# shiva.net
KiCad netlist of a schematic drawn in EAGLE
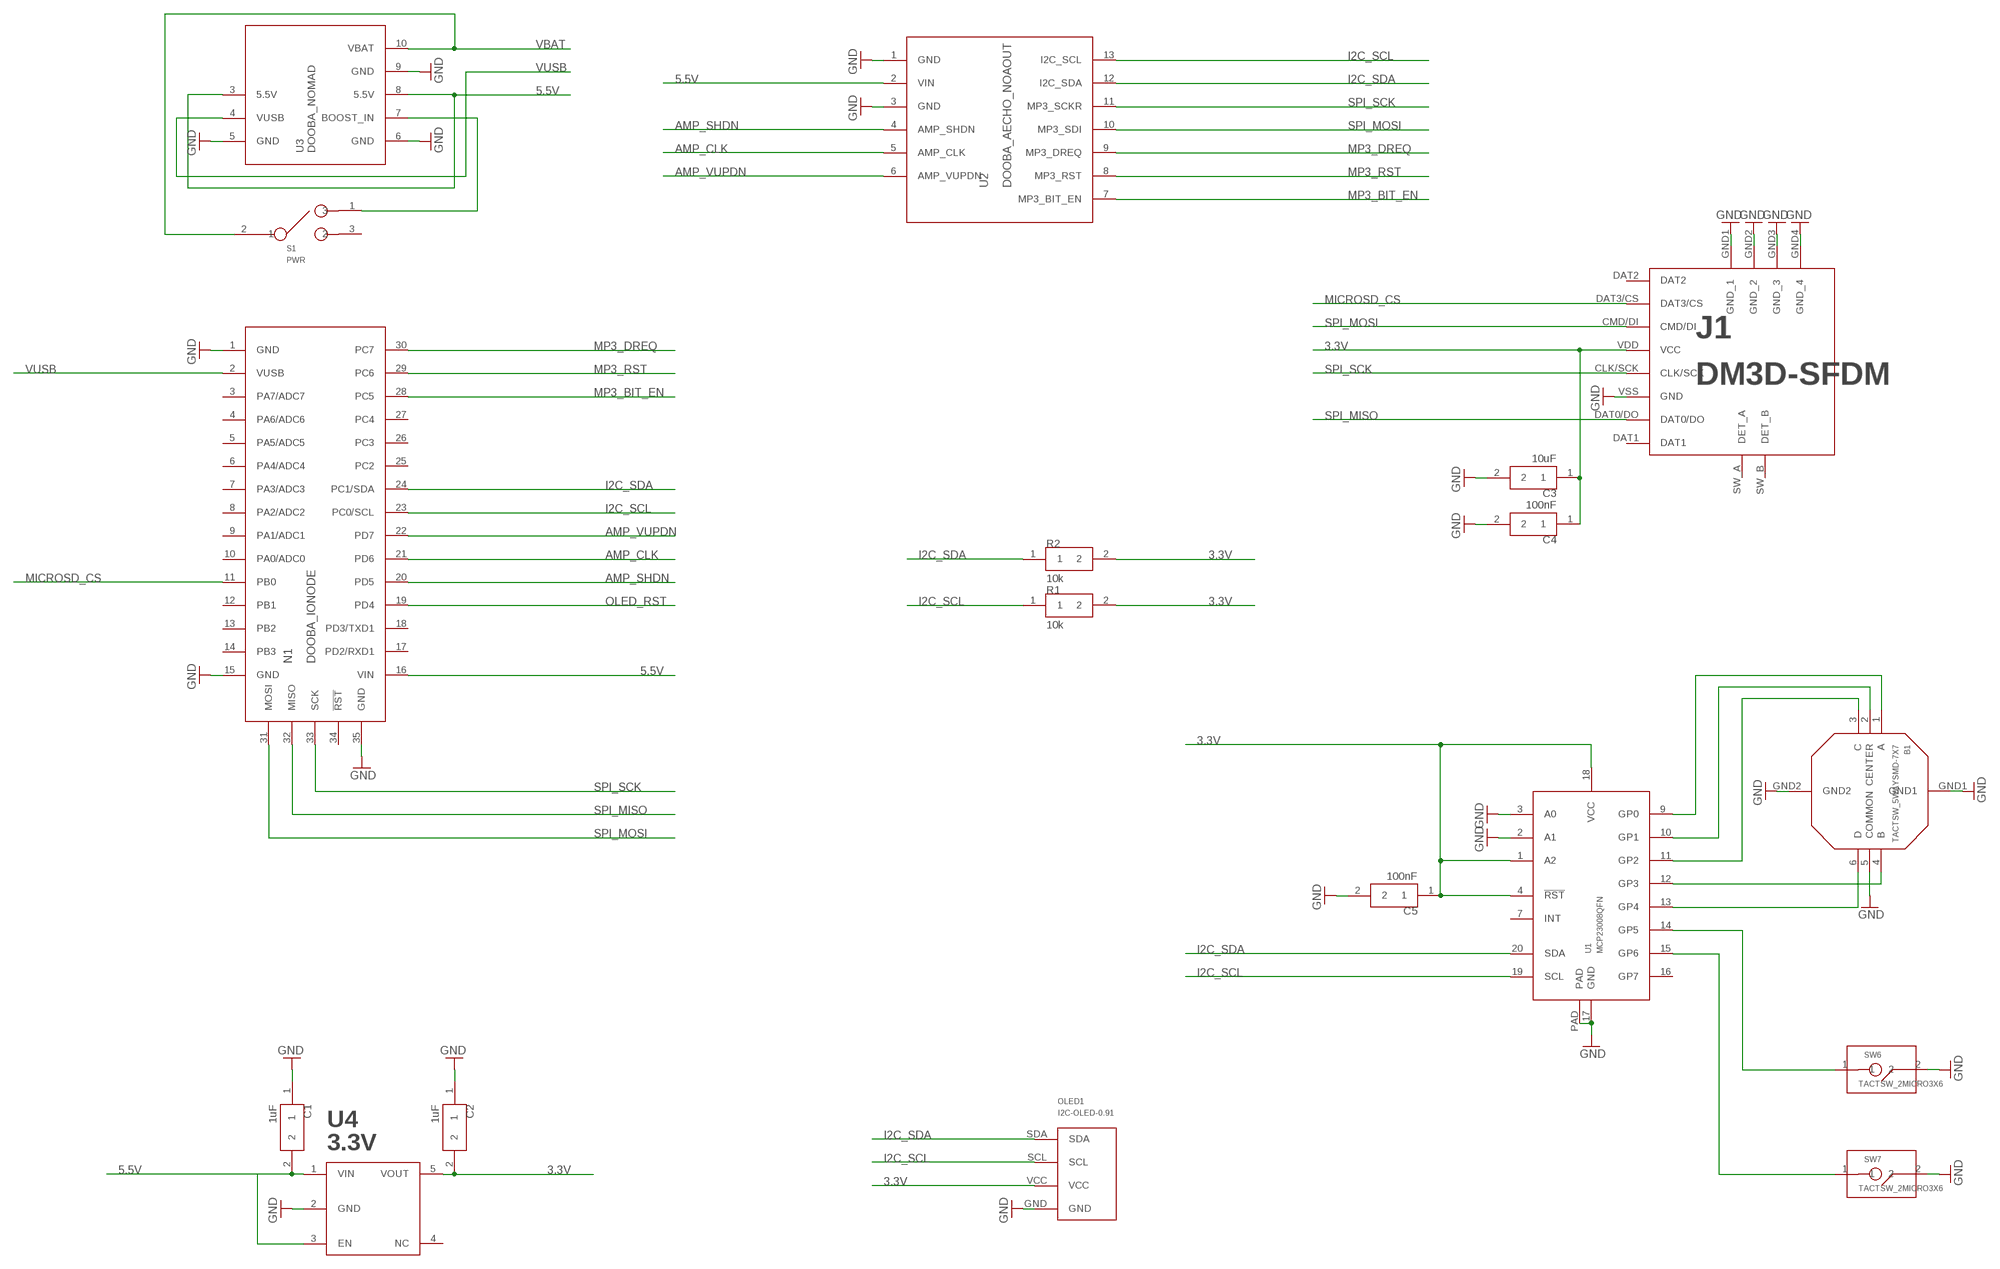
[diagram p0: schematic, sheet 1]

(export (version "E")
  (design (tool "Eeschema 10.0.6"))
  (components
    (comp (ref "B1")
      (value "TACTSW_5WAYSMD-7X7")
      (footprint "eagle-import:TACTSW-5WAY-7X7")
      (libsource (lib "eagle-import") (part "TACTSW_5WAYSMD-7X7"))
    )
    (comp (ref "C1")
      (value "1uF")
      (footprint "eagle-import:0805")
      (libsource (lib "eagle-import") (part "CAP0805"))
    )
    (comp (ref "C2")
      (value "1uF")
      (footprint "eagle-import:0805")
      (libsource (lib "eagle-import") (part "CAP0805"))
    )
    (comp (ref "C3")
      (value "10uF")
      (footprint "eagle-import:0805")
      (libsource (lib "eagle-import") (part "CAP0805"))
    )
    (comp (ref "C4")
      (value "100nF")
      (footprint "eagle-import:0805")
      (libsource (lib "eagle-import") (part "CAP0805"))
    )
    (comp (ref "C5")
      (value "100nF")
      (footprint "eagle-import:0805")
      (libsource (lib "eagle-import") (part "CAP0805"))
    )
    (comp (ref "J1")
      (value "DM3D-SFDM")
      (footprint "eagle-import:DM3D-SF")
      (libsource (lib "eagle-import") (part "DM3D-SFDM"))
    )
    (comp (ref "N1")
      (value "DOOBA_IONODE")
      (footprint "eagle-import:DOOBA_IONODE")
      (libsource (lib "eagle-import") (part "DOOBA_IONODE"))
    )
    (comp (ref "OLED1")
      (value "I2C-OLED-0.91")
      (footprint "eagle-import:I2C-OLED-0.91")
      (libsource (lib "eagle-import") (part "I2C-OLED-0.91"))
    )
    (comp (ref "R1")
      (value "10k")
      (footprint "eagle-import:0805")
      (libsource (lib "eagle-import") (part "RES0805"))
    )
    (comp (ref "R2")
      (value "10k")
      (footprint "eagle-import:0805")
      (libsource (lib "eagle-import") (part "RES0805"))
    )
    (comp (ref "S1")
      (value "PWR")
      (footprint "eagle-import:JS102011")
      (libsource (lib "eagle-import") (part "SWITCH_SPDT"))
    )
    (comp (ref "SW6")
      (value "TACTSW_2MICRO3X6")
      (footprint "eagle-import:TACTSW_MICRO3X6")
      (libsource (lib "eagle-import") (part "TACTSW_2MICRO3X6"))
    )
    (comp (ref "SW7")
      (value "TACTSW_2MICRO3X6")
      (footprint "eagle-import:TACTSW_MICRO3X6")
      (libsource (lib "eagle-import") (part "TACTSW_2MICRO3X6"))
    )
    (comp (ref "U1")
      (value "MCP23008QFN")
      (footprint "eagle-import:20-VQFN")
      (libsource (lib "eagle-import") (part "MCP23008QFN"))
    )
    (comp (ref "U2")
      (value "DOOBA_AECHO_NOAOUT")
      (footprint "eagle-import:DOOBA_AECHO_NOAOUT")
      (libsource (lib "eagle-import") (part "DOOBA_AECHO_NOAOUT"))
    )
    (comp (ref "U3")
      (value "DOOBA_NOMAD")
      (footprint "eagle-import:DOOBA_NOMAD")
      (libsource (lib "eagle-import") (part "DOOBA_NOMAD"))
    )
    (comp (ref "U4")
      (value "3.3V")
      (footprint "eagle-import:SOT23-5")
      (libsource (lib "eagle-import") (part "LP3985SOT23-5"))
    )
  )
  (nets
    (net (code "1") (name "/3.3V") (class "Default")
      (node (ref "C2") (pin "2") (pinfunction "2_2") (pintype "bidirectional"))
      (node (ref "C3") (pin "1") (pinfunction "1_1") (pintype "bidirectional"))
      (node (ref "C4") (pin "1") (pinfunction "1_1") (pintype "bidirectional"))
      (node (ref "C5") (pin "1") (pinfunction "1_1") (pintype "bidirectional"))
      (node (ref "J1") (pin "VDD") (pinfunction "VCC_VDD") (pintype "bidirectional"))
      (node (ref "OLED1") (pin "VCC") (pinfunction "VCC_VCC") (pintype "bidirectional"))
      (node (ref "R1") (pin "2") (pinfunction "2_2") (pintype "bidirectional"))
      (node (ref "R2") (pin "2") (pinfunction "2_2") (pintype "bidirectional"))
      (node (ref "U1") (pin "1") (pinfunction "A2_1") (pintype "bidirectional"))
      (node (ref "U1") (pin "18") (pinfunction "VCC_18") (pintype "bidirectional"))
      (node (ref "U1") (pin "4") (pinfunction "~{RST}_4") (pintype "bidirectional"))
      (node (ref "U4") (pin "5") (pinfunction "VOUT_5") (pintype "bidirectional"))
    )
    (net (code "2") (name "/5.5V") (class "Default")
      (node (ref "C1") (pin "2") (pinfunction "2_2") (pintype "bidirectional"))
      (node (ref "N1") (pin "16") (pinfunction "VIN_16") (pintype "bidirectional"))
      (node (ref "U2") (pin "2") (pinfunction "VIN_2") (pintype "bidirectional"))
      (node (ref "U3") (pin "3") (pinfunction "5.5V_3") (pintype "bidirectional"))
      (node (ref "U3") (pin "8") (pinfunction "5.5V_8") (pintype "bidirectional"))
      (node (ref "U4") (pin "1") (pinfunction "VIN_1") (pintype "bidirectional"))
      (node (ref "U4") (pin "3") (pinfunction "EN_3") (pintype "bidirectional"))
    )
    (net (code "3") (name "/AMP_CLK") (class "Default")
      (node (ref "N1") (pin "21") (pinfunction "PD6_21") (pintype "bidirectional"))
      (node (ref "U2") (pin "5") (pinfunction "AMP_CLK_5") (pintype "bidirectional"))
    )
    (net (code "4") (name "/AMP_SHDN") (class "Default")
      (node (ref "N1") (pin "20") (pinfunction "PD5_20") (pintype "bidirectional"))
      (node (ref "U2") (pin "4") (pinfunction "AMP_SHDN_4") (pintype "bidirectional"))
    )
    (net (code "5") (name "/AMP_VUPDN") (class "Default")
      (node (ref "N1") (pin "22") (pinfunction "PD7_22") (pintype "bidirectional"))
      (node (ref "U2") (pin "6") (pinfunction "AMP_VUPDN_6") (pintype "bidirectional"))
    )
    (net (code "6") (name "/I2C_SCL") (class "Default")
      (node (ref "N1") (pin "23") (pinfunction "PC0/SCL_23") (pintype "bidirectional"))
      (node (ref "OLED1") (pin "SCL") (pinfunction "SCL_SCL") (pintype "bidirectional"))
      (node (ref "R1") (pin "1") (pinfunction "1_1") (pintype "bidirectional"))
      (node (ref "U1") (pin "19") (pinfunction "SCL_19") (pintype "bidirectional"))
      (node (ref "U2") (pin "13") (pinfunction "I2C_SCL_13") (pintype "bidirectional"))
    )
    (net (code "7") (name "/I2C_SDA") (class "Default")
      (node (ref "N1") (pin "24") (pinfunction "PC1/SDA_24") (pintype "bidirectional"))
      (node (ref "OLED1") (pin "SDA") (pinfunction "SDA_SDA") (pintype "bidirectional"))
      (node (ref "R2") (pin "1") (pinfunction "1_1") (pintype "bidirectional"))
      (node (ref "U1") (pin "20") (pinfunction "SDA_20") (pintype "bidirectional"))
      (node (ref "U2") (pin "12") (pinfunction "I2C_SDA_12") (pintype "bidirectional"))
    )
    (net (code "8") (name "/MICROSD_CS") (class "Default")
      (node (ref "J1") (pin "DAT3/CS") (pinfunction "DAT3/CS_DAT3/CS") (pintype "bidirectional"))
      (node (ref "N1") (pin "11") (pinfunction "PB0_11") (pintype "bidirectional"))
    )
    (net (code "9") (name "/MP3_BIT_EN") (class "Default")
      (node (ref "N1") (pin "28") (pinfunction "PC5_28") (pintype "bidirectional"))
      (node (ref "U2") (pin "7") (pinfunction "MP3_BIT_EN_7") (pintype "bidirectional"))
    )
    (net (code "10") (name "/MP3_DREQ") (class "Default")
      (node (ref "N1") (pin "30") (pinfunction "PC7_30") (pintype "bidirectional"))
      (node (ref "U2") (pin "9") (pinfunction "MP3_DREQ_9") (pintype "bidirectional"))
    )
    (net (code "11") (name "/MP3_RST") (class "Default")
      (node (ref "N1") (pin "29") (pinfunction "PC6_29") (pintype "bidirectional"))
      (node (ref "U2") (pin "8") (pinfunction "MP3_RST_8") (pintype "bidirectional"))
    )
    (net (code "12") (name "/OLED_RST") (class "Default")
      (node (ref "N1") (pin "19") (pinfunction "PD4_19") (pintype "bidirectional"))
    )
    (net (code "13") (name "/SPI_MISO") (class "Default")
      (node (ref "J1") (pin "DAT0/DO") (pinfunction "DAT0/DO_DAT0/DO") (pintype "bidirectional"))
      (node (ref "N1") (pin "32") (pinfunction "MISO_32") (pintype "bidirectional"))
    )
    (net (code "14") (name "/SPI_MOSI") (class "Default")
      (node (ref "J1") (pin "CMD/DI") (pinfunction "CMD/DI_CMD/DI") (pintype "bidirectional"))
      (node (ref "N1") (pin "31") (pinfunction "MOSI_31") (pintype "bidirectional"))
      (node (ref "U2") (pin "10") (pinfunction "MP3_SDI_10") (pintype "bidirectional"))
    )
    (net (code "15") (name "/SPI_SCK") (class "Default")
      (node (ref "J1") (pin "CLK/SCK") (pinfunction "CLK/SCK_CLK/SCK") (pintype "bidirectional"))
      (node (ref "N1") (pin "33") (pinfunction "SCK_33") (pintype "bidirectional"))
      (node (ref "U2") (pin "11") (pinfunction "MP3_SCKR_11") (pintype "bidirectional"))
    )
    (net (code "16") (name "/VBAT") (class "Default")
      (node (ref "S1") (pin "2") (pinfunction "1_2") (pintype "bidirectional"))
      (node (ref "U3") (pin "10") (pinfunction "VBAT_10") (pintype "bidirectional"))
    )
    (net (code "17") (name "/VUSB") (class "Default")
      (node (ref "N1") (pin "2") (pinfunction "VUSB_2") (pintype "bidirectional"))
      (node (ref "U3") (pin "4") (pinfunction "VUSB_4") (pintype "bidirectional"))
    )
    (net (code "18") (name "GND") (class "Default")
      (node (ref "B1") (pin "5") (pinfunction "COMMON_5") (pintype "bidirectional"))
      (node (ref "B1") (pin "GND1") (pinfunction "GND1_GND1") (pintype "bidirectional"))
      (node (ref "B1") (pin "GND2") (pinfunction "GND2_GND2") (pintype "bidirectional"))
      (node (ref "C1") (pin "1") (pinfunction "1_1") (pintype "bidirectional"))
      (node (ref "C2") (pin "1") (pinfunction "1_1") (pintype "bidirectional"))
      (node (ref "C3") (pin "2") (pinfunction "2_2") (pintype "bidirectional"))
      (node (ref "C4") (pin "2") (pinfunction "2_2") (pintype "bidirectional"))
      (node (ref "C5") (pin "2") (pinfunction "2_2") (pintype "bidirectional"))
      (node (ref "J1") (pin "GND1") (pinfunction "GND_1_GND1") (pintype "bidirectional"))
      (node (ref "J1") (pin "GND2") (pinfunction "GND_2_GND2") (pintype "bidirectional"))
      (node (ref "J1") (pin "GND3") (pinfunction "GND_3_GND3") (pintype "bidirectional"))
      (node (ref "J1") (pin "GND4") (pinfunction "GND_4_GND4") (pintype "bidirectional"))
      (node (ref "J1") (pin "VSS") (pinfunction "GND_VSS") (pintype "bidirectional"))
      (node (ref "N1") (pin "1") (pinfunction "GND_1") (pintype "bidirectional"))
      (node (ref "N1") (pin "15") (pinfunction "GND_15") (pintype "bidirectional"))
      (node (ref "N1") (pin "35") (pinfunction "GND_35") (pintype "bidirectional"))
      (node (ref "OLED1") (pin "GND") (pinfunction "GND_GND") (pintype "bidirectional"))
      (node (ref "SW6") (pin "2") (pinfunction "2_2") (pintype "bidirectional"))
      (node (ref "SW7") (pin "2") (pinfunction "2_2") (pintype "bidirectional"))
      (node (ref "U1") (pin "17") (pinfunction "GND_17") (pintype "bidirectional"))
      (node (ref "U1") (pin "2") (pinfunction "A1_2") (pintype "bidirectional"))
      (node (ref "U1") (pin "3") (pinfunction "A0_3") (pintype "bidirectional"))
      (node (ref "U1") (pin "PAD") (pinfunction "PAD_PAD") (pintype "bidirectional"))
      (node (ref "U2") (pin "1") (pinfunction "GND_1") (pintype "bidirectional"))
      (node (ref "U2") (pin "3") (pinfunction "GND_3") (pintype "bidirectional"))
      (node (ref "U3") (pin "5") (pinfunction "GND_5") (pintype "bidirectional"))
      (node (ref "U3") (pin "6") (pinfunction "GND_6") (pintype "bidirectional"))
      (node (ref "U3") (pin "9") (pinfunction "GND_9") (pintype "bidirectional"))
      (node (ref "U4") (pin "2") (pinfunction "GND_2") (pintype "bidirectional"))
    )
    (net (code "19") (name "Net-(B1-A)") (class "Default")
      (node (ref "B1") (pin "1") (pinfunction "A_1") (pintype "bidirectional"))
      (node (ref "U1") (pin "9") (pinfunction "GP0_9") (pintype "bidirectional"))
    )
    (net (code "20") (name "Net-(B1-B)") (class "Default")
      (node (ref "B1") (pin "4") (pinfunction "B_4") (pintype "bidirectional"))
      (node (ref "U1") (pin "12") (pinfunction "GP3_12") (pintype "bidirectional"))
    )
    (net (code "21") (name "Net-(B1-C)") (class "Default")
      (node (ref "B1") (pin "3") (pinfunction "C_3") (pintype "bidirectional"))
      (node (ref "U1") (pin "11") (pinfunction "GP2_11") (pintype "bidirectional"))
    )
    (net (code "22") (name "Net-(B1-CENTER)") (class "Default")
      (node (ref "B1") (pin "2") (pinfunction "CENTER_2") (pintype "bidirectional"))
      (node (ref "U1") (pin "10") (pinfunction "GP1_10") (pintype "bidirectional"))
    )
    (net (code "23") (name "Net-(B1-D)") (class "Default")
      (node (ref "B1") (pin "6") (pinfunction "D_6") (pintype "bidirectional"))
      (node (ref "U1") (pin "13") (pinfunction "GP4_13") (pintype "bidirectional"))
    )
    (net (code "24") (name "Net-(S1-3)") (class "Default")
      (node (ref "S1") (pin "1") (pinfunction "3_1") (pintype "bidirectional"))
      (node (ref "U3") (pin "7") (pinfunction "BOOST_IN_7") (pintype "bidirectional"))
    )
    (net (code "25") (name "Net-(U1-GP5)") (class "Default")
      (node (ref "SW6") (pin "1") (pinfunction "1_1") (pintype "bidirectional"))
      (node (ref "U1") (pin "14") (pinfunction "GP5_14") (pintype "bidirectional"))
    )
    (net (code "26") (name "Net-(U1-GP6)") (class "Default")
      (node (ref "SW7") (pin "1") (pinfunction "1_1") (pintype "bidirectional"))
      (node (ref "U1") (pin "15") (pinfunction "GP6_15") (pintype "bidirectional"))
    )
    (net (code "27") (name "unconnected-(J1-DET_A-PadSW_A)") (class "Default")
      (node (ref "J1") (pin "SW_A") (pinfunction "DET_A_SW_A") (pintype "bidirectional"))
    )
    (net (code "28") (name "unconnected-(J1-DET_B-PadSW_B)") (class "Default")
      (node (ref "J1") (pin "SW_B") (pinfunction "DET_B_SW_B") (pintype "bidirectional"))
    )
    (net (code "29") (name "unconnected-(J1-PadDAT1)") (class "Default")
      (node (ref "J1") (pin "DAT1") (pinfunction "DAT1_DAT1") (pintype "bidirectional"))
    )
    (net (code "30") (name "unconnected-(J1-PadDAT2)") (class "Default")
      (node (ref "J1") (pin "DAT2") (pinfunction "DAT2_DAT2") (pintype "bidirectional"))
    )
    (net (code "31") (name "unconnected-(N1-PA0{slash}ADC0-Pad10)") (class "Default")
      (node (ref "N1") (pin "10") (pinfunction "PA0/ADC0_10") (pintype "bidirectional"))
    )
    (net (code "32") (name "unconnected-(N1-PA1{slash}ADC1-Pad9)") (class "Default")
      (node (ref "N1") (pin "9") (pinfunction "PA1/ADC1_9") (pintype "bidirectional"))
    )
    (net (code "33") (name "unconnected-(N1-PA2{slash}ADC2-Pad8)") (class "Default")
      (node (ref "N1") (pin "8") (pinfunction "PA2/ADC2_8") (pintype "bidirectional"))
    )
    (net (code "34") (name "unconnected-(N1-PA3{slash}ADC3-Pad7)") (class "Default")
      (node (ref "N1") (pin "7") (pinfunction "PA3/ADC3_7") (pintype "bidirectional"))
    )
    (net (code "35") (name "unconnected-(N1-PA4{slash}ADC4-Pad6)") (class "Default")
      (node (ref "N1") (pin "6") (pinfunction "PA4/ADC4_6") (pintype "bidirectional"))
    )
    (net (code "36") (name "unconnected-(N1-PA5{slash}ADC5-Pad5)") (class "Default")
      (node (ref "N1") (pin "5") (pinfunction "PA5/ADC5_5") (pintype "bidirectional"))
    )
    (net (code "37") (name "unconnected-(N1-PA6{slash}ADC6-Pad4)") (class "Default")
      (node (ref "N1") (pin "4") (pinfunction "PA6/ADC6_4") (pintype "bidirectional"))
    )
    (net (code "38") (name "unconnected-(N1-PA7{slash}ADC7-Pad3)") (class "Default")
      (node (ref "N1") (pin "3") (pinfunction "PA7/ADC7_3") (pintype "bidirectional"))
    )
    (net (code "39") (name "unconnected-(N1-PB1-Pad12)") (class "Default")
      (node (ref "N1") (pin "12") (pinfunction "PB1_12") (pintype "bidirectional"))
    )
    (net (code "40") (name "unconnected-(N1-PB2-Pad13)") (class "Default")
      (node (ref "N1") (pin "13") (pinfunction "PB2_13") (pintype "bidirectional"))
    )
    (net (code "41") (name "unconnected-(N1-PB3-Pad14)") (class "Default")
      (node (ref "N1") (pin "14") (pinfunction "PB3_14") (pintype "bidirectional"))
    )
    (net (code "42") (name "unconnected-(N1-PC2-Pad25)") (class "Default")
      (node (ref "N1") (pin "25") (pinfunction "PC2_25") (pintype "bidirectional"))
    )
    (net (code "43") (name "unconnected-(N1-PC3-Pad26)") (class "Default")
      (node (ref "N1") (pin "26") (pinfunction "PC3_26") (pintype "bidirectional"))
    )
    (net (code "44") (name "unconnected-(N1-PC4-Pad27)") (class "Default")
      (node (ref "N1") (pin "27") (pinfunction "PC4_27") (pintype "bidirectional"))
    )
    (net (code "45") (name "unconnected-(N1-PD2{slash}RXD1-Pad17)") (class "Default")
      (node (ref "N1") (pin "17") (pinfunction "PD2/RXD1_17") (pintype "bidirectional"))
    )
    (net (code "46") (name "unconnected-(N1-PD3{slash}TXD1-Pad18)") (class "Default")
      (node (ref "N1") (pin "18") (pinfunction "PD3/TXD1_18") (pintype "bidirectional"))
    )
    (net (code "47") (name "unconnected-(N1-~{RST}-Pad34)") (class "Default")
      (node (ref "N1") (pin "34") (pinfunction "~{RST}_34") (pintype "bidirectional"))
    )
    (net (code "48") (name "unconnected-(S1-2-Pad3)") (class "Default")
      (node (ref "S1") (pin "3") (pinfunction "2_3") (pintype "bidirectional"))
    )
    (net (code "49") (name "unconnected-(U1-GP7-Pad16)") (class "Default")
      (node (ref "U1") (pin "16") (pinfunction "GP7_16") (pintype "bidirectional"))
    )
    (net (code "50") (name "unconnected-(U1-INT-Pad7)") (class "Default")
      (node (ref "U1") (pin "7") (pinfunction "INT_7") (pintype "bidirectional"))
    )
    (net (code "51") (name "unconnected-(U4-NC-Pad4)") (class "Default")
      (node (ref "U4") (pin "4") (pinfunction "NC_4") (pintype "bidirectional"))
    )
  )
)
